# BMS_Design_1_New_Part_Monitor.net
KiCad netlist of a schematic drawn in Altium Designer
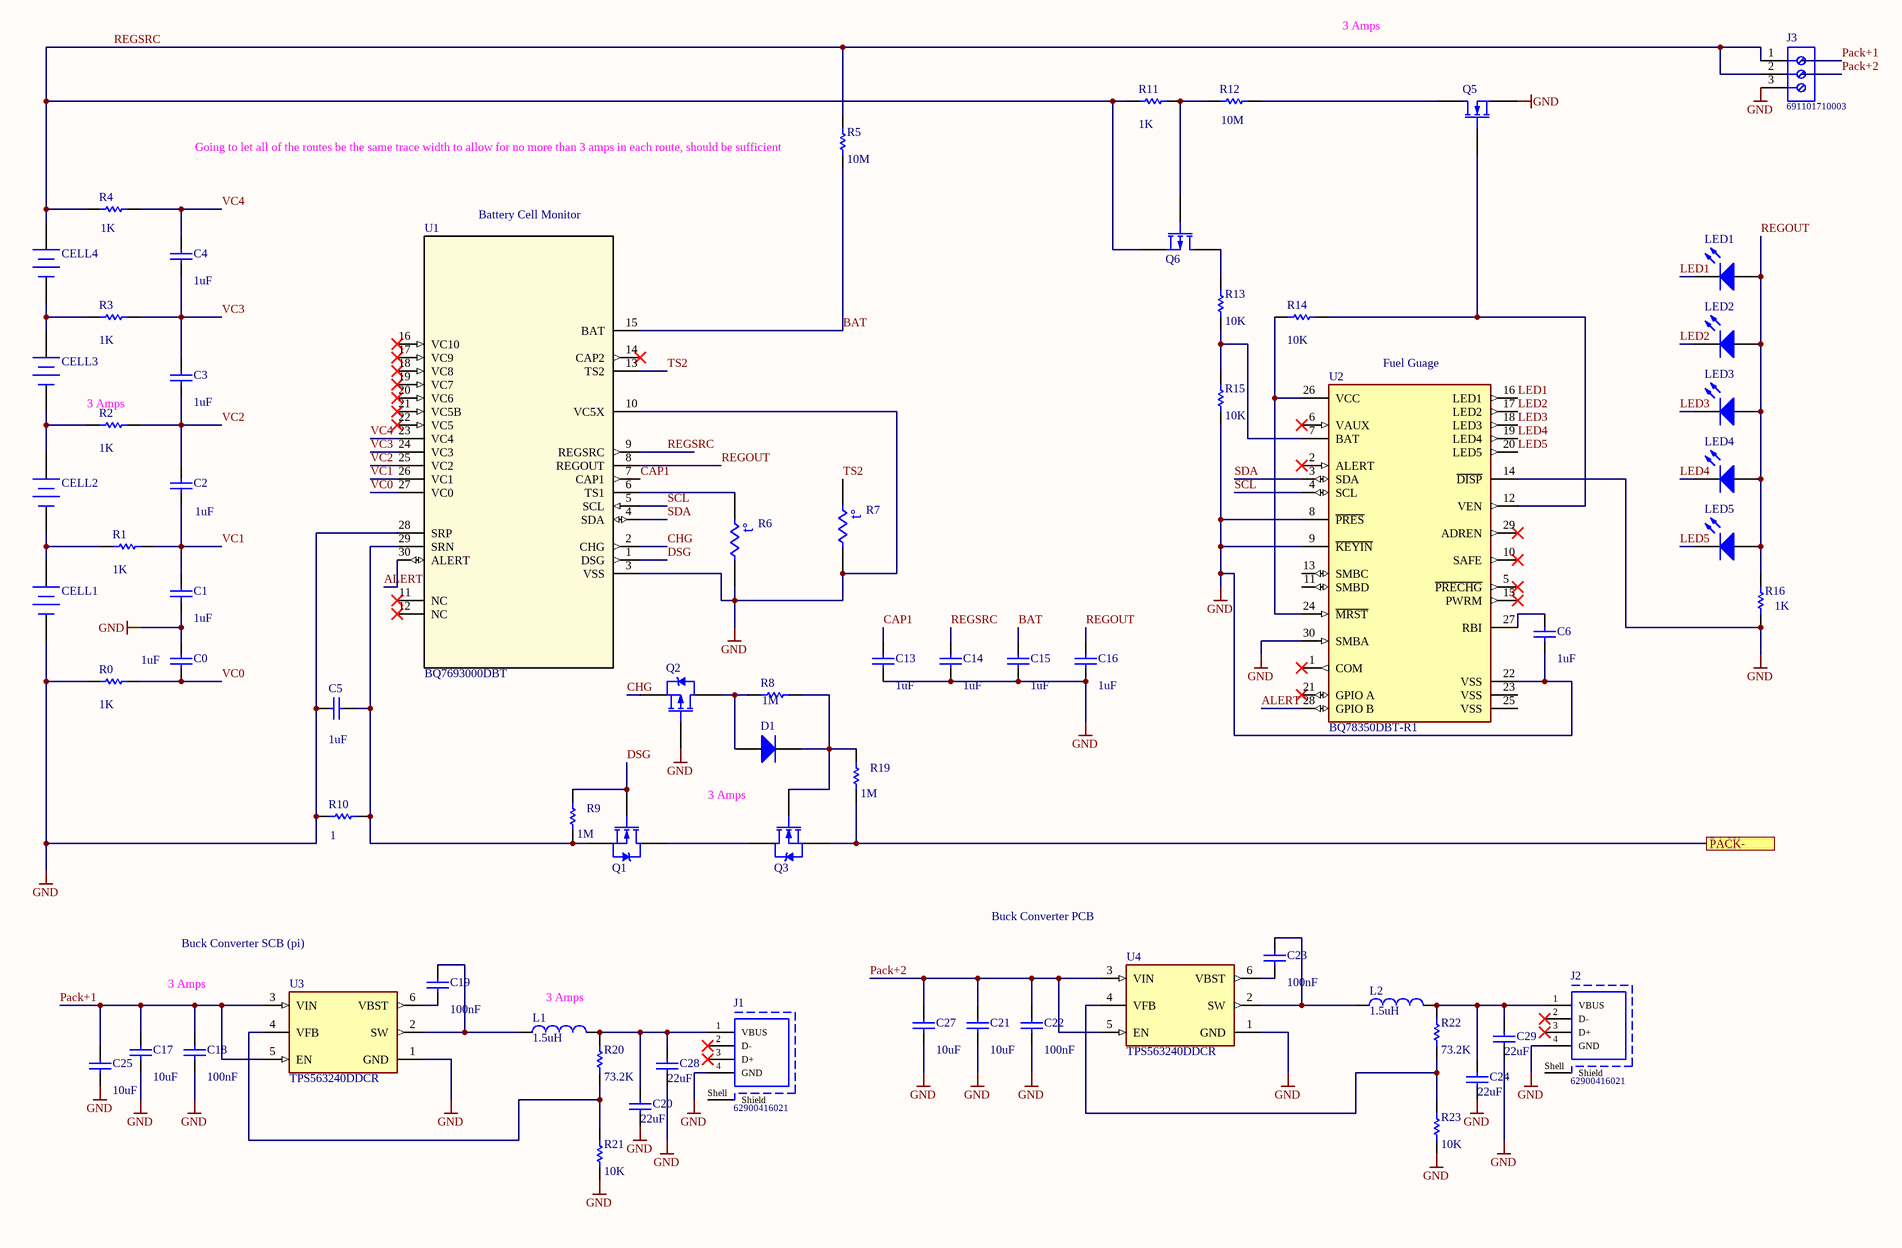
[diagram p0: BMS Design 1 New Part Monitor.SchDoc]

(export (version "E")
  (design (tool "Eeschema 10.0.6"))
  (components
    (comp (ref "C0")
      (value "1uF")
      (footprint "RAD-0.3")
      (description "Capacitor")
      (fields (field (name "PUBLISHER") "Altium Limited"))
      (libsource (lib "Miscellaneous Devices") (part "Cap"))
    )
    (comp (ref "C1")
      (value "1uF")
      (footprint "RAD-0.3")
      (description "Capacitor")
      (fields (field (name "PUBLISHER") "Altium Limited"))
      (libsource (lib "Miscellaneous Devices") (part "Cap"))
    )
    (comp (ref "C2")
      (value "1uF")
      (footprint "RAD-0.3")
      (description "Capacitor")
      (fields (field (name "PUBLISHER") "Altium Limited"))
      (libsource (lib "Miscellaneous Devices") (part "Cap"))
    )
    (comp (ref "C3")
      (value "1uF")
      (footprint "RAD-0.3")
      (description "Capacitor")
      (fields (field (name "PUBLISHER") "Altium Limited"))
      (libsource (lib "Miscellaneous Devices") (part "Cap"))
    )
    (comp (ref "C4")
      (value "1uF")
      (footprint "RAD-0.3")
      (description "Capacitor")
      (fields (field (name "PUBLISHER") "Altium Limited"))
      (libsource (lib "Miscellaneous Devices") (part "Cap"))
    )
    (comp (ref "C5")
      (value "1uF")
      (footprint "RAD-0.3")
      (description "Capacitor")
      (fields (field (name "PUBLISHER") "Altium Limited"))
      (libsource (lib "Miscellaneous Devices") (part "Cap"))
    )
    (comp (ref "C6")
      (value "1uF")
      (footprint "RAD-0.3")
      (description "Capacitor")
      (fields (field (name "PUBLISHER") "Altium Limited"))
      (libsource (lib "Miscellaneous Devices") (part "Cap"))
    )
    (comp (ref "C13")
      (value "1uF")
      (footprint "RAD-0.3")
      (description "Capacitor")
      (fields (field (name "PUBLISHER") "Altium Limited"))
      (libsource (lib "Miscellaneous Devices") (part "Cap"))
    )
    (comp (ref "C14")
      (value "1uF")
      (footprint "RAD-0.3")
      (description "Capacitor")
      (fields (field (name "PUBLISHER") "Altium Limited"))
      (libsource (lib "Miscellaneous Devices") (part "Cap"))
    )
    (comp (ref "C15")
      (value "1uF")
      (footprint "RAD-0.3")
      (description "Capacitor")
      (fields (field (name "PUBLISHER") "Altium Limited"))
      (libsource (lib "Miscellaneous Devices") (part "Cap"))
    )
    (comp (ref "C16")
      (value "1uF")
      (footprint "RAD-0.3")
      (description "Capacitor")
      (fields (field (name "PUBLISHER") "Altium Limited"))
      (libsource (lib "Miscellaneous Devices") (part "Cap"))
    )
    (comp (ref "C17")
      (value "10uF")
      (footprint "RAD-0.3")
      (description "Capacitor")
      (fields (field (name "PUBLISHER") "Altium Limited"))
      (libsource (lib "Miscellaneous Devices") (part "Cap"))
    )
    (comp (ref "C18")
      (value "100nF")
      (footprint "RAD-0.3")
      (description "Capacitor")
      (fields (field (name "PUBLISHER") "Altium Limited"))
      (libsource (lib "Miscellaneous Devices") (part "Cap"))
    )
    (comp (ref "C19")
      (value "100nF")
      (footprint "RAD-0.3")
      (description "Capacitor")
      (fields (field (name "PUBLISHER") "Altium Limited"))
      (libsource (lib "Miscellaneous Devices") (part "Cap"))
    )
    (comp (ref "C20")
      (value "22uF")
      (footprint "RAD-0.3")
      (description "Capacitor")
      (fields (field (name "PUBLISHER") "Altium Limited"))
      (libsource (lib "Miscellaneous Devices") (part "Cap"))
    )
    (comp (ref "C21")
      (value "10uF")
      (footprint "RAD-0.3")
      (description "Capacitor")
      (fields (field (name "PUBLISHER") "Altium Limited"))
      (libsource (lib "Miscellaneous Devices") (part "Cap"))
    )
    (comp (ref "C22")
      (value "100nF")
      (footprint "RAD-0.3")
      (description "Capacitor")
      (fields (field (name "PUBLISHER") "Altium Limited"))
      (libsource (lib "Miscellaneous Devices") (part "Cap"))
    )
    (comp (ref "C23")
      (value "100nF")
      (footprint "RAD-0.3")
      (description "Capacitor")
      (fields (field (name "PUBLISHER") "Altium Limited"))
      (libsource (lib "Miscellaneous Devices") (part "Cap"))
    )
    (comp (ref "C24")
      (value "22uF")
      (footprint "RAD-0.3")
      (description "Capacitor")
      (fields (field (name "PUBLISHER") "Altium Limited"))
      (libsource (lib "Miscellaneous Devices") (part "Cap"))
    )
    (comp (ref "C25")
      (value "10uF")
      (footprint "RAD-0.3")
      (description "Capacitor")
      (fields (field (name "PUBLISHER") "Altium Limited"))
      (libsource (lib "Miscellaneous Devices") (part "Cap"))
    )
    (comp (ref "C27")
      (value "10uF")
      (footprint "RAD-0.3")
      (description "Capacitor")
      (fields (field (name "PUBLISHER") "Altium Limited"))
      (libsource (lib "Miscellaneous Devices") (part "Cap"))
    )
    (comp (ref "C28")
      (value "22uF")
      (footprint "RAD-0.3")
      (description "Capacitor")
      (fields (field (name "PUBLISHER") "Altium Limited"))
      (libsource (lib "Miscellaneous Devices") (part "Cap"))
    )
    (comp (ref "C29")
      (value "22uF")
      (footprint "RAD-0.3")
      (description "Capacitor")
      (fields (field (name "PUBLISHER") "Altium Limited"))
      (libsource (lib "Miscellaneous Devices") (part "Cap"))
    )
    (comp (ref "CELL1")
      (value "~")
      (footprint "BAT-2")
      (description "Multicell Battery")
      (fields (field (name "PUBLISHER") "Altium Limited"))
      (libsource (lib "Miscellaneous Devices") (part "Battery"))
    )
    (comp (ref "CELL2")
      (value "~")
      (footprint "BAT-2")
      (description "Multicell Battery")
      (fields (field (name "PUBLISHER") "Altium Limited"))
      (libsource (lib "Miscellaneous Devices") (part "Battery"))
    )
    (comp (ref "CELL3")
      (value "~")
      (footprint "BAT-2")
      (description "Multicell Battery")
      (fields (field (name "PUBLISHER") "Altium Limited"))
      (libsource (lib "Miscellaneous Devices") (part "Battery"))
    )
    (comp (ref "CELL4")
      (value "~")
      (footprint "BAT-2")
      (description "Multicell Battery")
      (fields (field (name "PUBLISHER") "Altium Limited"))
      (libsource (lib "Miscellaneous Devices") (part "Battery"))
    )
    (comp (ref "D1")
      (value "~")
      (footprint "SMC")
      (description "Default Diode")
      (fields (field (name "PUBLISHER") "Altium Limited"))
      (libsource (lib "Miscellaneous Devices") (part "Diode"))
    )
    (comp (ref "J1")
      (value "62900416021")
      (footprint "62900416021")
      (description "USB 2.0 Type A Receptacle WR-COM, Horizontal, SMT")
      (fields (field (name "MANUFACTURER") "Wurth Elektronik") (field (name "PUBLISHER") "WurthElektronik"))
      (libsource (lib "Altium Content Vault") (part "WE-USB-4-1SHLD"))
    )
    (comp (ref "J2")
      (value "62900416021")
      (footprint "62900416021")
      (description "USB 2.0 Type A Receptacle WR-COM, Horizontal, SMT")
      (fields (field (name "MANUFACTURER") "Wurth Elektronik") (field (name "PUBLISHER") "WurthElektronik"))
      (libsource (lib "Altium Content Vault") (part "WE-USB-4-1SHLD"))
    )
    (comp (ref "J3")
      (value "691101710003")
      (footprint "691101710003")
      (description "Series 101 - 5.00 mm Horizontal Entry Modular with Pressure Clamp WR-TBL, 3 pin")
      (fields (field (name "MANUFACTURER") "Wurth Elektronik") (field (name "PUBLISHER") "WurthElektronik"))
      (libsource (lib "Altium Content Vault") (part "WE-CN-1P-F-TB3"))
    )
    (comp (ref "L1")
      (value "1.5uH")
      (footprint "0402-A")
      (description "Inductor")
      (fields (field (name "PUBLISHER") "Altium Limited"))
      (libsource (lib "Miscellaneous Devices") (part "Inductor"))
    )
    (comp (ref "L2")
      (value "1.5uH")
      (footprint "0402-A")
      (description "Inductor")
      (fields (field (name "PUBLISHER") "Altium Limited"))
      (libsource (lib "Miscellaneous Devices") (part "Inductor"))
    )
    (comp (ref "LED1")
      (value "~")
      (footprint "LED-0")
      (description "Typical INFRARED GaAs LED")
      (fields (field (name "PUBLISHER") "Altium Limited"))
      (libsource (lib "Miscellaneous Devices") (part "LED0"))
    )
    (comp (ref "LED2")
      (value "~")
      (footprint "LED-0")
      (description "Typical INFRARED GaAs LED")
      (fields (field (name "PUBLISHER") "Altium Limited"))
      (libsource (lib "Miscellaneous Devices") (part "LED0"))
    )
    (comp (ref "LED3")
      (value "~")
      (footprint "LED-0")
      (description "Typical INFRARED GaAs LED")
      (fields (field (name "PUBLISHER") "Altium Limited"))
      (libsource (lib "Miscellaneous Devices") (part "LED0"))
    )
    (comp (ref "LED4")
      (value "~")
      (footprint "LED-0")
      (description "Typical INFRARED GaAs LED")
      (fields (field (name "PUBLISHER") "Altium Limited"))
      (libsource (lib "Miscellaneous Devices") (part "LED0"))
    )
    (comp (ref "LED5")
      (value "~")
      (footprint "LED-0")
      (description "Typical INFRARED GaAs LED")
      (fields (field (name "PUBLISHER") "Altium Limited"))
      (libsource (lib "Miscellaneous Devices") (part "LED0"))
    )
    (comp (ref "Q1")
      (value "~")
      (footprint "TO-220AB")
      (description "N-Channel Power MOSFET")
      (fields (field (name "PUBLISHER") "Altium Limited"))
      (libsource (lib "Miscellaneous Devices") (part "NMOS-2"))
    )
    (comp (ref "Q2")
      (value "~")
      (footprint "TO-220AB")
      (description "P-Channel Power MOSFET")
      (fields (field (name "PUBLISHER") "Altium Limited"))
      (libsource (lib "Miscellaneous Devices") (part "PMOS-2"))
    )
    (comp (ref "Q3")
      (value "~")
      (footprint "TO-220AB")
      (description "N-Channel Power MOSFET")
      (fields (field (name "PUBLISHER") "Altium Limited"))
      (libsource (lib "Miscellaneous Devices") (part "NMOS-2"))
    )
    (comp (ref "Q5")
      (value "~")
      (footprint "E3")
      (description "N-Channel MOSFET")
      (fields (field (name "PUBLISHER") "Altium Limited"))
      (libsource (lib "Miscellaneous Devices") (part "MOSFET-N"))
    )
    (comp (ref "Q6")
      (value "~")
      (footprint "E3")
      (description "P-Channel MOSFET")
      (fields (field (name "PUBLISHER") "Altium Limited"))
      (libsource (lib "Miscellaneous Devices") (part "MOSFET-P"))
    )
    (comp (ref "R0")
      (value "1K")
      (footprint "AXIAL-0.3")
      (description "Resistor")
      (fields (field (name "PUBLISHER") "Altium Limited"))
      (libsource (lib "Miscellaneous Devices") (part "Res1"))
    )
    (comp (ref "R1")
      (value "1K")
      (footprint "AXIAL-0.3")
      (description "Resistor")
      (fields (field (name "PUBLISHER") "Altium Limited"))
      (libsource (lib "Miscellaneous Devices") (part "Res1"))
    )
    (comp (ref "R2")
      (value "1K")
      (footprint "AXIAL-0.3")
      (description "Resistor")
      (fields (field (name "PUBLISHER") "Altium Limited"))
      (libsource (lib "Miscellaneous Devices") (part "Res1"))
    )
    (comp (ref "R3")
      (value "1K")
      (footprint "AXIAL-0.3")
      (description "Resistor")
      (fields (field (name "PUBLISHER") "Altium Limited"))
      (libsource (lib "Miscellaneous Devices") (part "Res1"))
    )
    (comp (ref "R4")
      (value "1K")
      (footprint "AXIAL-0.3")
      (description "Resistor")
      (fields (field (name "PUBLISHER") "Altium Limited"))
      (libsource (lib "Miscellaneous Devices") (part "Res1"))
    )
    (comp (ref "R5")
      (value "10M")
      (footprint "AXIAL-0.3")
      (description "Resistor")
      (fields (field (name "PUBLISHER") "Altium Limited"))
      (libsource (lib "Miscellaneous Devices") (part "Res1"))
    )
    (comp (ref "R6")
      (value "~")
      (footprint "6-0805_N")
      (description "Thermistor")
      (fields (field (name "PUBLISHER") "Altium Limited"))
      (libsource (lib "Miscellaneous Devices") (part "Res Thermal"))
    )
    (comp (ref "R7")
      (value "~")
      (footprint "6-0805_N")
      (description "Thermistor")
      (fields (field (name "PUBLISHER") "Altium Limited"))
      (libsource (lib "Miscellaneous Devices") (part "Res Thermal"))
    )
    (comp (ref "R8")
      (value "1M")
      (footprint "AXIAL-0.3")
      (description "Resistor")
      (fields (field (name "PUBLISHER") "Altium Limited"))
      (libsource (lib "Miscellaneous Devices") (part "Res1"))
    )
    (comp (ref "R9")
      (value "1M")
      (footprint "AXIAL-0.3")
      (description "Resistor")
      (fields (field (name "PUBLISHER") "Altium Limited"))
      (libsource (lib "Miscellaneous Devices") (part "Res1"))
    )
    (comp (ref "R10")
      (value "~")
      (footprint "AXIAL-0.3")
      (description "Resistor")
      (fields (field (name "R10") "1") (field (name "PUBLISHER") "Altium Limited"))
      (libsource (lib "Miscellaneous Devices") (part "Res1"))
    )
    (comp (ref "R11")
      (value "1K")
      (footprint "AXIAL-0.3")
      (description "Resistor")
      (fields (field (name "PUBLISHER") "Altium Limited"))
      (libsource (lib "Miscellaneous Devices") (part "Res1"))
    )
    (comp (ref "R12")
      (value "10M")
      (footprint "AXIAL-0.3")
      (description "Resistor")
      (fields (field (name "PUBLISHER") "Altium Limited"))
      (libsource (lib "Miscellaneous Devices") (part "Res1"))
    )
    (comp (ref "R13")
      (value "10K")
      (footprint "AXIAL-0.3")
      (description "Resistor")
      (fields (field (name "PUBLISHER") "Altium Limited"))
      (libsource (lib "Miscellaneous Devices") (part "Res1"))
    )
    (comp (ref "R14")
      (value "10K")
      (footprint "AXIAL-0.3")
      (description "Resistor")
      (fields (field (name "PUBLISHER") "Altium Limited"))
      (libsource (lib "Miscellaneous Devices") (part "Res1"))
    )
    (comp (ref "R15")
      (value "10K")
      (footprint "AXIAL-0.3")
      (description "Resistor")
      (fields (field (name "PUBLISHER") "Altium Limited"))
      (libsource (lib "Miscellaneous Devices") (part "Res1"))
    )
    (comp (ref "R16")
      (value "1K")
      (footprint "AXIAL-0.3")
      (description "Resistor")
      (fields (field (name "PUBLISHER") "Altium Limited"))
      (libsource (lib "Miscellaneous Devices") (part "Res1"))
    )
    (comp (ref "R19")
      (value "1M")
      (footprint "AXIAL-0.3")
      (description "Resistor")
      (fields (field (name "PUBLISHER") "Altium Limited"))
      (libsource (lib "Miscellaneous Devices") (part "Res1"))
    )
    (comp (ref "R20")
      (value "73.2K")
      (footprint "AXIAL-0.3")
      (description "Resistor")
      (fields (field (name "PUBLISHER") "Altium Limited"))
      (libsource (lib "Miscellaneous Devices") (part "Res1"))
    )
    (comp (ref "R21")
      (value "10K")
      (footprint "AXIAL-0.3")
      (description "Resistor")
      (fields (field (name "PUBLISHER") "Altium Limited"))
      (libsource (lib "Miscellaneous Devices") (part "Res1"))
    )
    (comp (ref "R22")
      (value "73.2K")
      (footprint "AXIAL-0.3")
      (description "Resistor")
      (fields (field (name "PUBLISHER") "Altium Limited"))
      (libsource (lib "Miscellaneous Devices") (part "Res1"))
    )
    (comp (ref "R23")
      (value "10K")
      (footprint "AXIAL-0.3")
      (description "Resistor")
      (fields (field (name "PUBLISHER") "Altium Limited"))
      (libsource (lib "Miscellaneous Devices") (part "Res1"))
    )
    (comp (ref "U1")
      (value "BQ7693000DBT")
      (footprint "BQ7693000DBT:DBT0030A_N")
      (description "No Description Available")
      (fields (field (name "COPYRIGHT") "Copyright (C) 2022 Ultra Librarian. All rights reserved."))
      (libsource (lib "BQ7693000DBT") (part "BQ7693000DBT"))
    )
    (comp (ref "U2")
      (value "BQ78350DBT-R1")
      (footprint "FP-DBT0030A-IPC_C")
      (description "IC BATTERY MGMT CTRLR 30TSSOP")
      (libsource (lib "Altium Content Vault") (part "ce2f43281ae33b5194046e95201acc2"))
    )
    (comp (ref "U3")
      (value "TPS563240DDCR")
      (footprint "FP-DDC0006A-MFG")
      (description "IC REG CTRLR")
      (libsource (lib "Altium Content Vault") (part "c6d9e7010a909a6b76b4e29aba6d7cb"))
    )
    (comp (ref "U4")
      (value "TPS563240DDCR")
      (footprint "FP-DDC0006A-MFG")
      (description "IC REG CTRLR")
      (libsource (lib "Altium Content Vault") (part "c6d9e7010a909a6b76b4e29aba6d7cb"))
    )
  )
  (nets
    (net (code "1") (name "/ALERT") (class "Default")
      (node (ref "U1") (pin "30") (pinfunction "ALERT_30") (pintype "bidirectional"))
      (node (ref "U2") (pin "28") (pinfunction "GPIO_B_28") (pintype "bidirectional"))
    )
    (net (code "2") (name "/BAT") (class "Default")
      (node (ref "C15") (pin "2") (pinfunction "2_2") (pintype "passive"))
      (node (ref "R5") (pin "1") (pinfunction "1_1") (pintype "passive"))
      (node (ref "U1") (pin "15") (pinfunction "BAT_15") (pintype "power_in"))
    )
    (net (code "3") (name "/CAP1") (class "Default")
      (node (ref "C13") (pin "2") (pinfunction "2_2") (pintype "passive"))
      (node (ref "U1") (pin "7") (pinfunction "CAP1_7") (pintype "output"))
    )
    (net (code "4") (name "/CHG") (class "Default")
      (node (ref "Q2") (pin "3") (pinfunction "S_3") (pintype "passive"))
      (node (ref "U1") (pin "2") (pinfunction "CHG_2") (pintype "output"))
    )
    (net (code "5") (name "/DSG") (class "Default")
      (node (ref "Q1") (pin "1") (pinfunction "G_1") (pintype "passive"))
      (node (ref "R9") (pin "2") (pinfunction "2_2") (pintype "passive"))
      (node (ref "U1") (pin "1") (pinfunction "DSG_1") (pintype "output"))
    )
    (net (code "6") (name "/LED1") (class "Default")
      (node (ref "LED1") (pin "2") (pinfunction "K_2") (pintype "passive"))
      (node (ref "U2") (pin "16") (pinfunction "LED1_16") (pintype "output"))
    )
    (net (code "7") (name "/LED2") (class "Default")
      (node (ref "LED2") (pin "2") (pinfunction "K_2") (pintype "passive"))
      (node (ref "U2") (pin "17") (pinfunction "LED2_17") (pintype "output"))
    )
    (net (code "8") (name "/LED3") (class "Default")
      (node (ref "LED3") (pin "2") (pinfunction "K_2") (pintype "passive"))
      (node (ref "U2") (pin "18") (pinfunction "LED3_18") (pintype "output"))
    )
    (net (code "9") (name "/LED4") (class "Default")
      (node (ref "LED4") (pin "2") (pinfunction "K_2") (pintype "passive"))
      (node (ref "U2") (pin "19") (pinfunction "LED4_19") (pintype "output"))
    )
    (net (code "10") (name "/LED5") (class "Default")
      (node (ref "LED5") (pin "2") (pinfunction "K_2") (pintype "passive"))
      (node (ref "U2") (pin "20") (pinfunction "LED5_20") (pintype "output"))
    )
    (net (code "11") (name "/PACK-") (class "Default")
      (node (ref "Q3") (pin "3") (pinfunction "S_3") (pintype "passive"))
      (node (ref "R19") (pin "1") (pinfunction "1_1") (pintype "passive"))
    )
    (net (code "12") (name "/Pack+1") (class "Default")
      (node (ref "C17") (pin "2") (pinfunction "2_2") (pintype "passive"))
      (node (ref "C18") (pin "2") (pinfunction "2_2") (pintype "passive"))
      (node (ref "C25") (pin "2") (pinfunction "2_2") (pintype "passive"))
      (node (ref "U3") (pin "3") (pinfunction "VIN_3") (pintype "input"))
      (node (ref "U3") (pin "5") (pinfunction "EN_5") (pintype "input"))
    )
    (net (code "13") (name "/Pack+2") (class "Default")
      (node (ref "C21") (pin "2") (pinfunction "2_2") (pintype "passive"))
      (node (ref "C22") (pin "2") (pinfunction "2_2") (pintype "passive"))
      (node (ref "C27") (pin "2") (pinfunction "2_2") (pintype "passive"))
      (node (ref "U4") (pin "3") (pinfunction "VIN_3") (pintype "input"))
      (node (ref "U4") (pin "5") (pinfunction "EN_5") (pintype "input"))
    )
    (net (code "14") (name "/REGOUT") (class "Default")
      (node (ref "C16") (pin "2") (pinfunction "2_2") (pintype "passive"))
      (node (ref "LED1") (pin "1") (pinfunction "A_1") (pintype "passive"))
      (node (ref "LED2") (pin "1") (pinfunction "A_1") (pintype "passive"))
      (node (ref "LED3") (pin "1") (pinfunction "A_1") (pintype "passive"))
      (node (ref "LED4") (pin "1") (pinfunction "A_1") (pintype "passive"))
      (node (ref "LED5") (pin "1") (pinfunction "A_1") (pintype "passive"))
      (node (ref "R16") (pin "2") (pinfunction "2_2") (pintype "passive"))
      (node (ref "U1") (pin "8") (pinfunction "REGOUT_8") (pintype "power_in"))
    )
    (net (code "15") (name "/REGSRC") (class "Default")
      (node (ref "C14") (pin "2") (pinfunction "2_2") (pintype "passive"))
      (node (ref "CELL4") (pin "1") (pinfunction "+_1") (pintype "passive"))
      (node (ref "J3") (pin "1") (pinfunction "1_1") (pintype "passive"))
      (node (ref "J3") (pin "2") (pinfunction "2_2") (pintype "passive"))
      (node (ref "Q6") (pin "3") (pinfunction "S_3") (pintype "passive"))
      (node (ref "R11") (pin "1") (pinfunction "1_1") (pintype "passive"))
      (node (ref "R4") (pin "1") (pinfunction "1_1") (pintype "passive"))
      (node (ref "R5") (pin "2") (pinfunction "2_2") (pintype "passive"))
      (node (ref "U1") (pin "9") (pinfunction "REGSRC_9") (pintype "output"))
    )
    (net (code "16") (name "/SCL") (class "Default")
      (node (ref "U1") (pin "5") (pinfunction "SCL_5") (pintype "input"))
      (node (ref "U2") (pin "4") (pinfunction "SCL_4") (pintype "bidirectional"))
    )
    (net (code "17") (name "/SDA") (class "Default")
      (node (ref "U1") (pin "4") (pinfunction "SDA_4") (pintype "bidirectional"))
      (node (ref "U2") (pin "3") (pinfunction "SDA_3") (pintype "bidirectional"))
    )
    (net (code "18") (name "/TS2") (class "Default")
      (node (ref "R7") (pin "1") (pinfunction "1_1") (pintype "passive"))
      (node (ref "U1") (pin "13") (pinfunction "TS2_13") (pintype "passive"))
    )
    (net (code "19") (name "/VC0") (class "Default")
      (node (ref "C0") (pin "1") (pinfunction "1_1") (pintype "passive"))
      (node (ref "R0") (pin "2") (pinfunction "2_2") (pintype "passive"))
      (node (ref "U1") (pin "27") (pinfunction "VC0_27") (pintype "passive"))
    )
    (net (code "20") (name "/VC1") (class "Default")
      (node (ref "C1") (pin "2") (pinfunction "2_2") (pintype "passive"))
      (node (ref "C2") (pin "1") (pinfunction "1_1") (pintype "passive"))
      (node (ref "R1") (pin "2") (pinfunction "2_2") (pintype "passive"))
      (node (ref "U1") (pin "26") (pinfunction "VC1_26") (pintype "passive"))
    )
    (net (code "21") (name "/VC2") (class "Default")
      (node (ref "C2") (pin "2") (pinfunction "2_2") (pintype "passive"))
      (node (ref "C3") (pin "1") (pinfunction "1_1") (pintype "passive"))
      (node (ref "R2") (pin "2") (pinfunction "2_2") (pintype "passive"))
      (node (ref "U1") (pin "25") (pinfunction "VC2_25") (pintype "passive"))
    )
    (net (code "22") (name "/VC3") (class "Default")
      (node (ref "C3") (pin "2") (pinfunction "2_2") (pintype "passive"))
      (node (ref "C4") (pin "1") (pinfunction "1_1") (pintype "passive"))
      (node (ref "R3") (pin "2") (pinfunction "2_2") (pintype "passive"))
      (node (ref "U1") (pin "24") (pinfunction "VC3_24") (pintype "passive"))
    )
    (net (code "23") (name "/VC4") (class "Default")
      (node (ref "C4") (pin "2") (pinfunction "2_2") (pintype "passive"))
      (node (ref "R4") (pin "2") (pinfunction "2_2") (pintype "passive"))
      (node (ref "U1") (pin "23") (pinfunction "VC4_23") (pintype "passive"))
    )
    (net (code "24") (name "GND") (class "Default")
      (node (ref "C0") (pin "2") (pinfunction "2_2") (pintype "passive"))
      (node (ref "C1") (pin "1") (pinfunction "1_1") (pintype "passive"))
      (node (ref "C13") (pin "1") (pinfunction "1_1") (pintype "passive"))
      (node (ref "C14") (pin "1") (pinfunction "1_1") (pintype "passive"))
      (node (ref "C15") (pin "1") (pinfunction "1_1") (pintype "passive"))
      (node (ref "C16") (pin "1") (pinfunction "1_1") (pintype "passive"))
      (node (ref "C17") (pin "1") (pinfunction "1_1") (pintype "passive"))
      (node (ref "C18") (pin "1") (pinfunction "1_1") (pintype "passive"))
      (node (ref "C20") (pin "1") (pinfunction "1_1") (pintype "passive"))
      (node (ref "C21") (pin "1") (pinfunction "1_1") (pintype "passive"))
      (node (ref "C22") (pin "1") (pinfunction "1_1") (pintype "passive"))
      (node (ref "C24") (pin "1") (pinfunction "1_1") (pintype "passive"))
      (node (ref "C25") (pin "1") (pinfunction "1_1") (pintype "passive"))
      (node (ref "C27") (pin "1") (pinfunction "1_1") (pintype "passive"))
      (node (ref "C28") (pin "1") (pinfunction "1_1") (pintype "passive"))
      (node (ref "C29") (pin "1") (pinfunction "1_1") (pintype "passive"))
      (node (ref "C5") (pin "1") (pinfunction "1_1") (pintype "passive"))
      (node (ref "C6") (pin "1") (pinfunction "1_1") (pintype "passive"))
      (node (ref "CELL1") (pin "2") (pinfunction "-_2") (pintype "passive"))
      (node (ref "J1") (pin "4") (pinfunction "GND_4") (pintype "passive"))
      (node (ref "J2") (pin "4") (pinfunction "GND_4") (pintype "passive"))
      (node (ref "J3") (pin "3") (pinfunction "3_3") (pintype "passive"))
      (node (ref "Q2") (pin "1") (pinfunction "G_1") (pintype "passive"))
      (node (ref "Q5") (pin "3") (pinfunction "S_3") (pintype "passive"))
      (node (ref "R0") (pin "1") (pinfunction "1_1") (pintype "passive"))
      (node (ref "R10") (pin "1") (pinfunction "1_1") (pintype "passive"))
      (node (ref "R15") (pin "1") (pinfunction "1_1") (pintype "passive"))
      (node (ref "R16") (pin "1") (pinfunction "1_1") (pintype "passive"))
      (node (ref "R21") (pin "1") (pinfunction "1_1") (pintype "passive"))
      (node (ref "R23") (pin "1") (pinfunction "1_1") (pintype "passive"))
      (node (ref "R6") (pin "2") (pinfunction "2_2") (pintype "passive"))
      (node (ref "R7") (pin "2") (pinfunction "2_2") (pintype "passive"))
      (node (ref "U1") (pin "10") (pinfunction "VC5X_10") (pintype "passive"))
      (node (ref "U1") (pin "28") (pinfunction "SRP_28") (pintype "passive"))
      (node (ref "U1") (pin "3") (pinfunction "VSS_3") (pintype "power_in"))
      (node (ref "U2") (pin "14") (pinfunction "~{DISP}_14") (pintype "passive"))
      (node (ref "U2") (pin "22") (pinfunction "VSS_22") (pintype "passive"))
      (node (ref "U2") (pin "30") (pinfunction "SMBA_30") (pintype "input"))
      (node (ref "U2") (pin "8") (pinfunction "~{PRES}_8") (pintype "passive"))
      (node (ref "U2") (pin "9") (pinfunction "~{KEYIN}_9") (pintype "passive"))
      (node (ref "U3") (pin "1") (pinfunction "GND_1") (pintype "passive"))
      (node (ref "U4") (pin "1") (pinfunction "GND_1") (pintype "passive"))
    )
    (net (code "25") (name "Net-(CELL1-+)") (class "Default")
      (node (ref "CELL1") (pin "1") (pinfunction "+_1") (pintype "passive"))
      (node (ref "CELL2") (pin "2") (pinfunction "-_2") (pintype "passive"))
      (node (ref "R1") (pin "1") (pinfunction "1_1") (pintype "passive"))
    )
    (net (code "26") (name "Net-(CELL2-+)") (class "Default")
      (node (ref "CELL2") (pin "1") (pinfunction "+_1") (pintype "passive"))
      (node (ref "CELL3") (pin "2") (pinfunction "-_2") (pintype "passive"))
      (node (ref "R2") (pin "1") (pinfunction "1_1") (pintype "passive"))
    )
    (net (code "27") (name "Net-(CELL3-+)") (class "Default")
      (node (ref "CELL3") (pin "1") (pinfunction "+_1") (pintype "passive"))
      (node (ref "CELL4") (pin "2") (pinfunction "-_2") (pintype "passive"))
      (node (ref "R3") (pin "1") (pinfunction "1_1") (pintype "passive"))
    )
    (net (code "28") (name "Net-(D1-A)") (class "Default")
      (node (ref "D1") (pin "1") (pinfunction "A_1") (pintype "passive"))
      (node (ref "Q2") (pin "2") (pinfunction "D_2") (pintype "passive"))
      (node (ref "R8") (pin "2") (pinfunction "2_2") (pintype "passive"))
    )
    (net (code "29") (name "Net-(D1-K)") (class "Default")
      (node (ref "D1") (pin "2") (pinfunction "K_2") (pintype "passive"))
      (node (ref "Q3") (pin "1") (pinfunction "G_1") (pintype "passive"))
      (node (ref "R19") (pin "2") (pinfunction "2_2") (pintype "passive"))
      (node (ref "R8") (pin "1") (pinfunction "1_1") (pintype "passive"))
    )
    (net (code "30") (name "Net-(J1-VBUS)") (class "Default")
      (node (ref "C20") (pin "2") (pinfunction "2_2") (pintype "passive"))
      (node (ref "C28") (pin "2") (pinfunction "2_2") (pintype "passive"))
      (node (ref "J1") (pin "1") (pinfunction "VBUS_1") (pintype "passive"))
      (node (ref "L1") (pin "2") (pinfunction "2_2") (pintype "passive"))
      (node (ref "R20") (pin "2") (pinfunction "2_2") (pintype "passive"))
    )
    (net (code "31") (name "Net-(J2-VBUS)") (class "Default")
      (node (ref "C24") (pin "2") (pinfunction "2_2") (pintype "passive"))
      (node (ref "C29") (pin "2") (pinfunction "2_2") (pintype "passive"))
      (node (ref "J2") (pin "1") (pinfunction "VBUS_1") (pintype "passive"))
      (node (ref "L2") (pin "2") (pinfunction "2_2") (pintype "passive"))
      (node (ref "R22") (pin "2") (pinfunction "2_2") (pintype "passive"))
    )
    (net (code "32") (name "Net-(Q1-D)") (class "Default")
      (node (ref "Q1") (pin "2") (pinfunction "D_2") (pintype "passive"))
      (node (ref "Q3") (pin "2") (pinfunction "D_2") (pintype "passive"))
    )
    (net (code "33") (name "Net-(Q1-S)") (class "Default")
      (node (ref "C5") (pin "2") (pinfunction "2_2") (pintype "passive"))
      (node (ref "Q1") (pin "3") (pinfunction "S_3") (pintype "passive"))
      (node (ref "R10") (pin "2") (pinfunction "2_2") (pintype "passive"))
      (node (ref "R9") (pin "1") (pinfunction "1_1") (pintype "passive"))
      (node (ref "U1") (pin "29") (pinfunction "SRN_29") (pintype "passive"))
    )
    (net (code "34") (name "Net-(Q5-D)") (class "Default")
      (node (ref "Q5") (pin "1") (pinfunction "D_1") (pintype "passive"))
      (node (ref "R12") (pin "2") (pinfunction "2_2") (pintype "passive"))
    )
    (net (code "35") (name "Net-(Q5-G)") (class "Default")
      (node (ref "Q5") (pin "2") (pinfunction "G_2") (pintype "passive"))
      (node (ref "R14") (pin "2") (pinfunction "2_2") (pintype "passive"))
      (node (ref "U2") (pin "12") (pinfunction "VEN_12") (pintype "output"))
    )
    (net (code "36") (name "Net-(Q6-D)") (class "Default")
      (node (ref "Q6") (pin "1") (pinfunction "D_1") (pintype "passive"))
      (node (ref "R13") (pin "2") (pinfunction "2_2") (pintype "passive"))
    )
    (net (code "37") (name "Net-(Q6-G)") (class "Default")
      (node (ref "Q6") (pin "2") (pinfunction "G_2") (pintype "passive"))
      (node (ref "R11") (pin "2") (pinfunction "2_2") (pintype "passive"))
      (node (ref "R12") (pin "1") (pinfunction "1_1") (pintype "passive"))
    )
    (net (code "38") (name "Net-(U1-TS1)") (class "Default")
      (node (ref "R6") (pin "1") (pinfunction "1_1") (pintype "passive"))
      (node (ref "U1") (pin "6") (pinfunction "TS1_6") (pintype "passive"))
    )
    (net (code "39") (name "Net-(U2-BAT)") (class "Default")
      (node (ref "R13") (pin "1") (pinfunction "1_1") (pintype "passive"))
      (node (ref "R15") (pin "2") (pinfunction "2_2") (pintype "passive"))
      (node (ref "U2") (pin "7") (pinfunction "BAT_7") (pintype "passive"))
    )
    (net (code "40") (name "Net-(U2-RBI)") (class "Default")
      (node (ref "C6") (pin "2") (pinfunction "2_2") (pintype "passive"))
      (node (ref "U2") (pin "27") (pinfunction "RBI_27") (pintype "power_in"))
    )
    (net (code "41") (name "Net-(U2-VCC)") (class "Default")
      (node (ref "R14") (pin "1") (pinfunction "1_1") (pintype "passive"))
      (node (ref "U2") (pin "24") (pinfunction "~{MRST}_24") (pintype "input"))
      (node (ref "U2") (pin "26") (pinfunction "VCC_26") (pintype "power_in"))
    )
    (net (code "42") (name "Net-(U3-SW)") (class "Default")
      (node (ref "C19") (pin "2") (pinfunction "2_2") (pintype "passive"))
      (node (ref "L1") (pin "1") (pinfunction "1_1") (pintype "passive"))
      (node (ref "U3") (pin "2") (pinfunction "SW_2") (pintype "output"))
    )
    (net (code "43") (name "Net-(U3-VBST)") (class "Default")
      (node (ref "C19") (pin "1") (pinfunction "1_1") (pintype "passive"))
      (node (ref "U3") (pin "6") (pinfunction "VBST_6") (pintype "output"))
    )
    (net (code "44") (name "Net-(U3-VFB)") (class "Default")
      (node (ref "R20") (pin "1") (pinfunction "1_1") (pintype "passive"))
      (node (ref "R21") (pin "2") (pinfunction "2_2") (pintype "passive"))
      (node (ref "U3") (pin "4") (pinfunction "VFB_4") (pintype "passive"))
    )
    (net (code "45") (name "Net-(U4-SW)") (class "Default")
      (node (ref "C23") (pin "2") (pinfunction "2_2") (pintype "passive"))
      (node (ref "L2") (pin "1") (pinfunction "1_1") (pintype "passive"))
      (node (ref "U4") (pin "2") (pinfunction "SW_2") (pintype "output"))
    )
    (net (code "46") (name "Net-(U4-VBST)") (class "Default")
      (node (ref "C23") (pin "1") (pinfunction "1_1") (pintype "passive"))
      (node (ref "U4") (pin "6") (pinfunction "VBST_6") (pintype "output"))
    )
    (net (code "47") (name "Net-(U4-VFB)") (class "Default")
      (node (ref "R22") (pin "1") (pinfunction "1_1") (pintype "passive"))
      (node (ref "R23") (pin "2") (pinfunction "2_2") (pintype "passive"))
      (node (ref "U4") (pin "4") (pinfunction "VFB_4") (pintype "passive"))
    )
    (net (code "48") (name "unconnected-(J1-D+-Pad3)") (class "Default")
      (node (ref "J1") (pin "3") (pinfunction "D+_3") (pintype "passive+no_connect"))
    )
    (net (code "49") (name "unconnected-(J1-D--Pad2)") (class "Default")
      (node (ref "J1") (pin "2") (pinfunction "D-_2") (pintype "passive+no_connect"))
    )
    (net (code "50") (name "unconnected-(J1-Shield-PadShell)") (class "Default")
      (node (ref "J1") (pin "Shell") (pinfunction "Shield_Shell") (pintype "passive"))
    )
    (net (code "51") (name "unconnected-(J2-D+-Pad3)") (class "Default")
      (node (ref "J2") (pin "3") (pinfunction "D+_3") (pintype "passive+no_connect"))
    )
    (net (code "52") (name "unconnected-(J2-D--Pad2)") (class "Default")
      (node (ref "J2") (pin "2") (pinfunction "D-_2") (pintype "passive+no_connect"))
    )
    (net (code "53") (name "unconnected-(J2-Shield-PadShell)") (class "Default")
      (node (ref "J2") (pin "Shell") (pinfunction "Shield_Shell") (pintype "passive"))
    )
    (net (code "54") (name "unconnected-(U1-CAP2-Pad14)") (class "Default")
      (node (ref "U1") (pin "14") (pinfunction "CAP2_14") (pintype "output+no_connect"))
    )
    (net (code "55") (name "unconnected-(U1-NC-Pad11)") (class "Default")
      (node (ref "U1") (pin "11") (pinfunction "NC_11") (pintype "passive+no_connect"))
    )
    (net (code "56") (name "unconnected-(U1-NC-Pad12)") (class "Default")
      (node (ref "U1") (pin "12") (pinfunction "NC_12") (pintype "passive+no_connect"))
    )
    (net (code "57") (name "unconnected-(U1-VC5-Pad22)") (class "Default")
      (node (ref "U1") (pin "22") (pinfunction "VC5_22") (pintype "input+no_connect"))
    )
    (net (code "58") (name "unconnected-(U1-VC5B-Pad21)") (class "Default")
      (node (ref "U1") (pin "21") (pinfunction "VC5B_21") (pintype "input+no_connect"))
    )
    (net (code "59") (name "unconnected-(U1-VC6-Pad20)") (class "Default")
      (node (ref "U1") (pin "20") (pinfunction "VC6_20") (pintype "input+no_connect"))
    )
    (net (code "60") (name "unconnected-(U1-VC7-Pad19)") (class "Default")
      (node (ref "U1") (pin "19") (pinfunction "VC7_19") (pintype "input+no_connect"))
    )
    (net (code "61") (name "unconnected-(U1-VC8-Pad18)") (class "Default")
      (node (ref "U1") (pin "18") (pinfunction "VC8_18") (pintype "input+no_connect"))
    )
    (net (code "62") (name "unconnected-(U1-VC9-Pad17)") (class "Default")
      (node (ref "U1") (pin "17") (pinfunction "VC9_17") (pintype "input+no_connect"))
    )
    (net (code "63") (name "unconnected-(U1-VC10-Pad16)") (class "Default")
      (node (ref "U1") (pin "16") (pinfunction "VC10_16") (pintype "input+no_connect"))
    )
    (net (code "64") (name "unconnected-(U2-ADREN-Pad29)") (class "Default")
      (node (ref "U2") (pin "29") (pinfunction "ADREN_29") (pintype "output+no_connect"))
    )
    (net (code "65") (name "unconnected-(U2-ALERT-Pad2)") (class "Default")
      (node (ref "U2") (pin "2") (pinfunction "ALERT_2") (pintype "input+no_connect"))
    )
    (net (code "66") (name "unconnected-(U2-COM-Pad1)") (class "Default")
      (node (ref "U2") (pin "1") (pinfunction "COM_1") (pintype "output+no_connect"))
    )
    (net (code "67") (name "unconnected-(U2-GPIO_A-Pad21)") (class "Default")
      (node (ref "U2") (pin "21") (pinfunction "GPIO_A_21") (pintype "bidirectional+no_connect"))
    )
    (net (code "68") (name "unconnected-(U2-PWRM-Pad15)") (class "Default")
      (node (ref "U2") (pin "15") (pinfunction "PWRM_15") (pintype "output+no_connect"))
    )
    (net (code "69") (name "unconnected-(U2-SAFE-Pad10)") (class "Default")
      (node (ref "U2") (pin "10") (pinfunction "SAFE_10") (pintype "output+no_connect"))
    )
    (net (code "70") (name "unconnected-(U2-SMBC-Pad13)") (class "Default")
      (node (ref "U2") (pin "13") (pinfunction "SMBC_13") (pintype "bidirectional"))
    )
    (net (code "71") (name "unconnected-(U2-SMBD-Pad11)") (class "Default")
      (node (ref "U2") (pin "11") (pinfunction "SMBD_11") (pintype "bidirectional"))
    )
    (net (code "72") (name "unconnected-(U2-VAUX-Pad6)") (class "Default")
      (node (ref "U2") (pin "6") (pinfunction "VAUX_6") (pintype "input+no_connect"))
    )
    (net (code "73") (name "unconnected-(U2-VSS-Pad23)") (class "Default")
      (node (ref "U2") (pin "23") (pinfunction "VSS_23") (pintype "power_in"))
    )
    (net (code "74") (name "unconnected-(U2-VSS-Pad25)") (class "Default")
      (node (ref "U2") (pin "25") (pinfunction "VSS_25") (pintype "power_in"))
    )
    (net (code "75") (name "unconnected-(U2-~{PRECHG}-Pad5)") (class "Default")
      (node (ref "U2") (pin "5") (pinfunction "~{PRECHG}_5") (pintype "output+no_connect"))
    )
  )
)
